# SNES_RGBAmp_wCSYNC.net
KiCad netlist of a schematic drawn in EAGLE
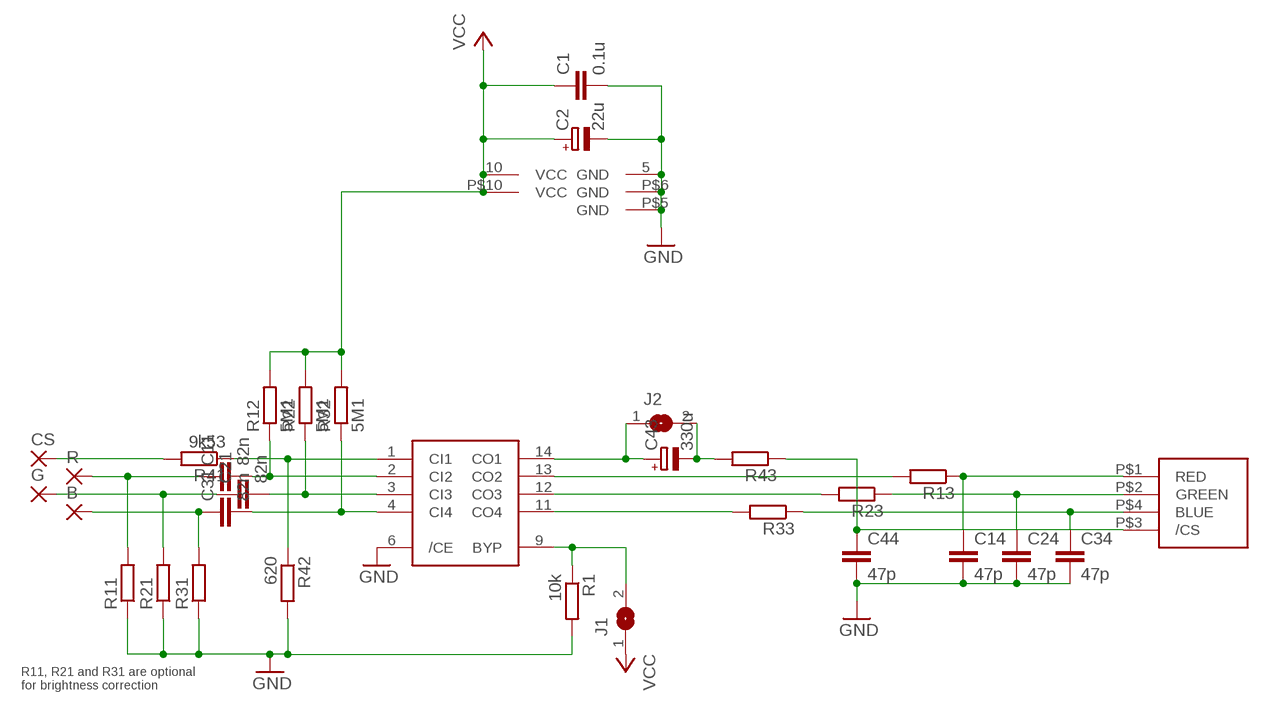
[diagram p0: schematic, sheet 1]

(export (version "E")
  (design (tool "Eeschema 10.0.6"))
  (components
    (comp (ref "B")
      (value "SMD2")
      (footprint "eagle-import:SMD1,27-2,54")
      (libsource (lib "eagle-import") (part "SMD2"))
    )
    (comp (ref "C1")
      (value "0.1u")
      (footprint "eagle-import:C0603K")
      (libsource (lib "eagle-import") (part "C-EUC0603K"))
    )
    (comp (ref "C2")
      (value "22u")
      (footprint "eagle-import:SMC_B")
      (libsource (lib "eagle-import") (part "CPOL-EUSMCB"))
    )
    (comp (ref "C11")
      (value "82n")
      (footprint "eagle-import:C0603K")
      (libsource (lib "eagle-import") (part "C-EUC0603K"))
    )
    (comp (ref "C14")
      (value "47p")
      (footprint "eagle-import:C0603K")
      (libsource (lib "eagle-import") (part "C-EUC0603K"))
    )
    (comp (ref "C21")
      (value "82n")
      (footprint "eagle-import:C0603K")
      (libsource (lib "eagle-import") (part "C-EUC0603K"))
    )
    (comp (ref "C24")
      (value "47p")
      (footprint "eagle-import:C0603K")
      (libsource (lib "eagle-import") (part "C-EUC0603K"))
    )
    (comp (ref "C31")
      (value "82n")
      (footprint "eagle-import:C0603K")
      (libsource (lib "eagle-import") (part "C-EUC0603K"))
    )
    (comp (ref "C34")
      (value "47p")
      (footprint "eagle-import:C0603K")
      (libsource (lib "eagle-import") (part "C-EUC0603K"))
    )
    (comp (ref "C43")
      (value "330u")
      (footprint "eagle-import:SMC_D")
      (libsource (lib "eagle-import") (part "CPOL-EUSMCD"))
    )
    (comp (ref "C44")
      (value "47p")
      (footprint "eagle-import:C0603K")
      (libsource (lib "eagle-import") (part "C-EUC0603K"))
    )
    (comp (ref "CS")
      (value "SMD2")
      (footprint "eagle-import:SMD1,27-2,54")
      (libsource (lib "eagle-import") (part "SMD2"))
    )
    (comp (ref "G")
      (value "SMD2")
      (footprint "eagle-import:SMD1,27-2,54")
      (libsource (lib "eagle-import") (part "SMD2"))
    )
    (comp (ref "J1") (value "SJ") (footprint "eagle-import:SJ") (libsource (lib "eagle-import") (part "SJ")))
    (comp (ref "J2") (value "SJ") (footprint "eagle-import:SJ") (libsource (lib "eagle-import") (part "SJ")))
    (comp (ref "J3")
      (value "SNES_MULTIAV_RGBC_ONLY")
      (footprint "eagle-import:SNES_MULTIAV_RGBC_ONLY")
      (libsource (lib "eagle-import") (part "SNES_MULTIAV_RGBC_ONLY"))
    )
    (comp (ref "R")
      (value "SMD2")
      (footprint "eagle-import:SMD1,27-2,54")
      (libsource (lib "eagle-import") (part "SMD2"))
    )
    (comp (ref "R1")
      (value "10k")
      (footprint "eagle-import:R0603")
      (libsource (lib "eagle-import") (part "R-EU_R0603"))
    )
    (comp (ref "R11")
      (value "R-EU_R0603")
      (footprint "eagle-import:R0603")
      (libsource (lib "eagle-import") (part "R-EU_R0603"))
    )
    (comp (ref "R12")
      (value "5M1")
      (footprint "eagle-import:R0603")
      (libsource (lib "eagle-import") (part "R-EU_R0603"))
    )
    (comp (ref "R13")
      (value "R-EU_R0603")
      (footprint "eagle-import:R0603")
      (libsource (lib "eagle-import") (part "R-EU_R0603"))
    )
    (comp (ref "R21")
      (value "R-EU_R0603")
      (footprint "eagle-import:R0603")
      (libsource (lib "eagle-import") (part "R-EU_R0603"))
    )
    (comp (ref "R22")
      (value "5M1")
      (footprint "eagle-import:R0603")
      (libsource (lib "eagle-import") (part "R-EU_R0603"))
    )
    (comp (ref "R23")
      (value "R-EU_R0603")
      (footprint "eagle-import:R0603")
      (libsource (lib "eagle-import") (part "R-EU_R0603"))
    )
    (comp (ref "R31")
      (value "R-EU_R0603")
      (footprint "eagle-import:R0603")
      (libsource (lib "eagle-import") (part "R-EU_R0603"))
    )
    (comp (ref "R32")
      (value "5M1")
      (footprint "eagle-import:R0603")
      (libsource (lib "eagle-import") (part "R-EU_R0603"))
    )
    (comp (ref "R33")
      (value "R-EU_R0603")
      (footprint "eagle-import:R0603")
      (libsource (lib "eagle-import") (part "R-EU_R0603"))
    )
    (comp (ref "R41")
      (value "9k53")
      (footprint "eagle-import:R0603")
      (libsource (lib "eagle-import") (part "R-EU_R0603"))
    )
    (comp (ref "R42")
      (value "620")
      (footprint "eagle-import:R0603")
      (libsource (lib "eagle-import") (part "R-EU_R0603"))
    )
    (comp (ref "R43")
      (value "R-EU_R0603")
      (footprint "eagle-import:R0603")
      (libsource (lib "eagle-import") (part "R-EU_R0603"))
    )
    (comp (ref "U1")
      (value "THS7374")
      (footprint "eagle-import:THS7374")
      (libsource (lib "eagle-import") (part "THS7374"))
    )
  )
  (nets
    (net (code "1") (name "GND") (class "Default")
      (node (ref "C1") (pin "2") (pinfunction "2_2") (pintype "passive"))
      (node (ref "C14") (pin "2") (pinfunction "2_2") (pintype "passive"))
      (node (ref "C2") (pin "-") (pinfunction "-_-") (pintype "passive"))
      (node (ref "C24") (pin "2") (pinfunction "2_2") (pintype "passive"))
      (node (ref "C34") (pin "2") (pinfunction "2_2") (pintype "passive"))
      (node (ref "C44") (pin "2") (pinfunction "2_2") (pintype "passive"))
      (node (ref "J3") (pin "P$5") (pinfunction "GND_P$5") (pintype "bidirectional"))
      (node (ref "J3") (pin "P$6") (pinfunction "GND_P$6") (pintype "bidirectional"))
      (node (ref "R1") (pin "2") (pinfunction "2_2") (pintype "passive"))
      (node (ref "R11") (pin "1") (pinfunction "1_1") (pintype "passive"))
      (node (ref "R21") (pin "1") (pinfunction "1_1") (pintype "passive"))
      (node (ref "R31") (pin "1") (pinfunction "1_1") (pintype "passive"))
      (node (ref "R42") (pin "2") (pinfunction "2_2") (pintype "passive"))
      (node (ref "U1") (pin "5") (pinfunction "GND_5") (pintype "bidirectional"))
      (node (ref "U1") (pin "6") (pinfunction "/CE_6") (pintype "bidirectional"))
    )
    (net (code "2") (name "Net-(B-P)") (class "Default")
      (node (ref "B") (pin "1") (pinfunction "P_1") (pintype "passive"))
      (node (ref "C31") (pin "1") (pinfunction "1_1") (pintype "passive"))
      (node (ref "R31") (pin "2") (pinfunction "2_2") (pintype "passive"))
    )
    (net (code "3") (name "Net-(C43-Pad-)") (class "Default")
      (node (ref "C43") (pin "-") (pinfunction "-_-") (pintype "passive"))
      (node (ref "J2") (pin "2") (pinfunction "2_2") (pintype "passive"))
      (node (ref "R43") (pin "2") (pinfunction "2_2") (pintype "passive"))
    )
    (net (code "4") (name "Net-(CS-P)") (class "Default")
      (node (ref "CS") (pin "1") (pinfunction "P_1") (pintype "passive"))
      (node (ref "R41") (pin "2") (pinfunction "2_2") (pintype "passive"))
    )
    (net (code "5") (name "Net-(G-P)") (class "Default")
      (node (ref "C21") (pin "1") (pinfunction "1_1") (pintype "passive"))
      (node (ref "G") (pin "1") (pinfunction "P_1") (pintype "passive"))
      (node (ref "R21") (pin "2") (pinfunction "2_2") (pintype "passive"))
    )
    (net (code "6") (name "Net-(J3A-BLUE)") (class "Default")
      (node (ref "C34") (pin "1") (pinfunction "1_1") (pintype "passive"))
      (node (ref "J3") (pin "P$4") (pinfunction "BLUE_P$4") (pintype "bidirectional"))
      (node (ref "R33") (pin "1") (pinfunction "1_1") (pintype "passive"))
    )
    (net (code "7") (name "Net-(J3A-GREEN)") (class "Default")
      (node (ref "C24") (pin "1") (pinfunction "1_1") (pintype "passive"))
      (node (ref "J3") (pin "P$2") (pinfunction "GREEN_P$2") (pintype "bidirectional"))
      (node (ref "R23") (pin "1") (pinfunction "1_1") (pintype "passive"))
    )
    (net (code "8") (name "Net-(J3A-RED)") (class "Default")
      (node (ref "C14") (pin "1") (pinfunction "1_1") (pintype "passive"))
      (node (ref "J3") (pin "P$1") (pinfunction "RED_P$1") (pintype "bidirectional"))
      (node (ref "R13") (pin "1") (pinfunction "1_1") (pintype "passive"))
    )
    (net (code "9") (name "Net-(J3A-{slash}CS)") (class "Default")
      (node (ref "C44") (pin "1") (pinfunction "1_1") (pintype "passive"))
      (node (ref "J3") (pin "P$3") (pinfunction "/CS_P$3") (pintype "bidirectional"))
      (node (ref "R43") (pin "1") (pinfunction "1_1") (pintype "passive"))
    )
    (net (code "10") (name "Net-(R-P)") (class "Default")
      (node (ref "C11") (pin "1") (pinfunction "1_1") (pintype "passive"))
      (node (ref "R") (pin "1") (pinfunction "P_1") (pintype "passive"))
      (node (ref "R11") (pin "2") (pinfunction "2_2") (pintype "passive"))
    )
    (net (code "11") (name "Net-(U1A-BYP)") (class "Default")
      (node (ref "J1") (pin "2") (pinfunction "2_2") (pintype "passive"))
      (node (ref "R1") (pin "1") (pinfunction "1_1") (pintype "passive"))
      (node (ref "U1") (pin "9") (pinfunction "BYP_9") (pintype "bidirectional"))
    )
    (net (code "12") (name "Net-(U1A-CI1)") (class "Default")
      (node (ref "R41") (pin "1") (pinfunction "1_1") (pintype "passive"))
      (node (ref "R42") (pin "1") (pinfunction "1_1") (pintype "passive"))
      (node (ref "U1") (pin "1") (pinfunction "CI1_1") (pintype "bidirectional"))
    )
    (net (code "13") (name "Net-(U1A-CI2)") (class "Default")
      (node (ref "C11") (pin "2") (pinfunction "2_2") (pintype "passive"))
      (node (ref "R12") (pin "1") (pinfunction "1_1") (pintype "passive"))
      (node (ref "U1") (pin "2") (pinfunction "CI2_2") (pintype "bidirectional"))
    )
    (net (code "14") (name "Net-(U1A-CI3)") (class "Default")
      (node (ref "C21") (pin "2") (pinfunction "2_2") (pintype "passive"))
      (node (ref "R22") (pin "1") (pinfunction "1_1") (pintype "passive"))
      (node (ref "U1") (pin "3") (pinfunction "CI3_3") (pintype "bidirectional"))
    )
    (net (code "15") (name "Net-(U1A-CI4)") (class "Default")
      (node (ref "C31") (pin "2") (pinfunction "2_2") (pintype "passive"))
      (node (ref "R32") (pin "1") (pinfunction "1_1") (pintype "passive"))
      (node (ref "U1") (pin "4") (pinfunction "CI4_4") (pintype "bidirectional"))
    )
    (net (code "16") (name "Net-(U1A-CO1)") (class "Default")
      (node (ref "C43") (pin "+") (pinfunction "+_+") (pintype "passive"))
      (node (ref "J2") (pin "1") (pinfunction "1_1") (pintype "passive"))
      (node (ref "U1") (pin "14") (pinfunction "CO1_14") (pintype "bidirectional"))
    )
    (net (code "17") (name "Net-(U1A-CO2)") (class "Default")
      (node (ref "R13") (pin "2") (pinfunction "2_2") (pintype "passive"))
      (node (ref "U1") (pin "13") (pinfunction "CO2_13") (pintype "bidirectional"))
    )
    (net (code "18") (name "Net-(U1A-CO3)") (class "Default")
      (node (ref "R23") (pin "2") (pinfunction "2_2") (pintype "passive"))
      (node (ref "U1") (pin "12") (pinfunction "CO3_12") (pintype "bidirectional"))
    )
    (net (code "19") (name "Net-(U1A-CO4)") (class "Default")
      (node (ref "R33") (pin "2") (pinfunction "2_2") (pintype "passive"))
      (node (ref "U1") (pin "11") (pinfunction "CO4_11") (pintype "bidirectional"))
    )
    (net (code "20") (name "VCC") (class "Default")
      (node (ref "C1") (pin "1") (pinfunction "1_1") (pintype "passive"))
      (node (ref "C2") (pin "+") (pinfunction "+_+") (pintype "passive"))
      (node (ref "J1") (pin "1") (pinfunction "1_1") (pintype "passive"))
      (node (ref "J3") (pin "P$10") (pinfunction "VCC_P$10") (pintype "bidirectional"))
      (node (ref "R12") (pin "2") (pinfunction "2_2") (pintype "passive"))
      (node (ref "R22") (pin "2") (pinfunction "2_2") (pintype "passive"))
      (node (ref "R32") (pin "2") (pinfunction "2_2") (pintype "passive"))
      (node (ref "U1") (pin "10") (pinfunction "VCC_10") (pintype "bidirectional"))
    )
  )
)
